# Power.net
KiCad netlist of a schematic drawn in Altium Designer
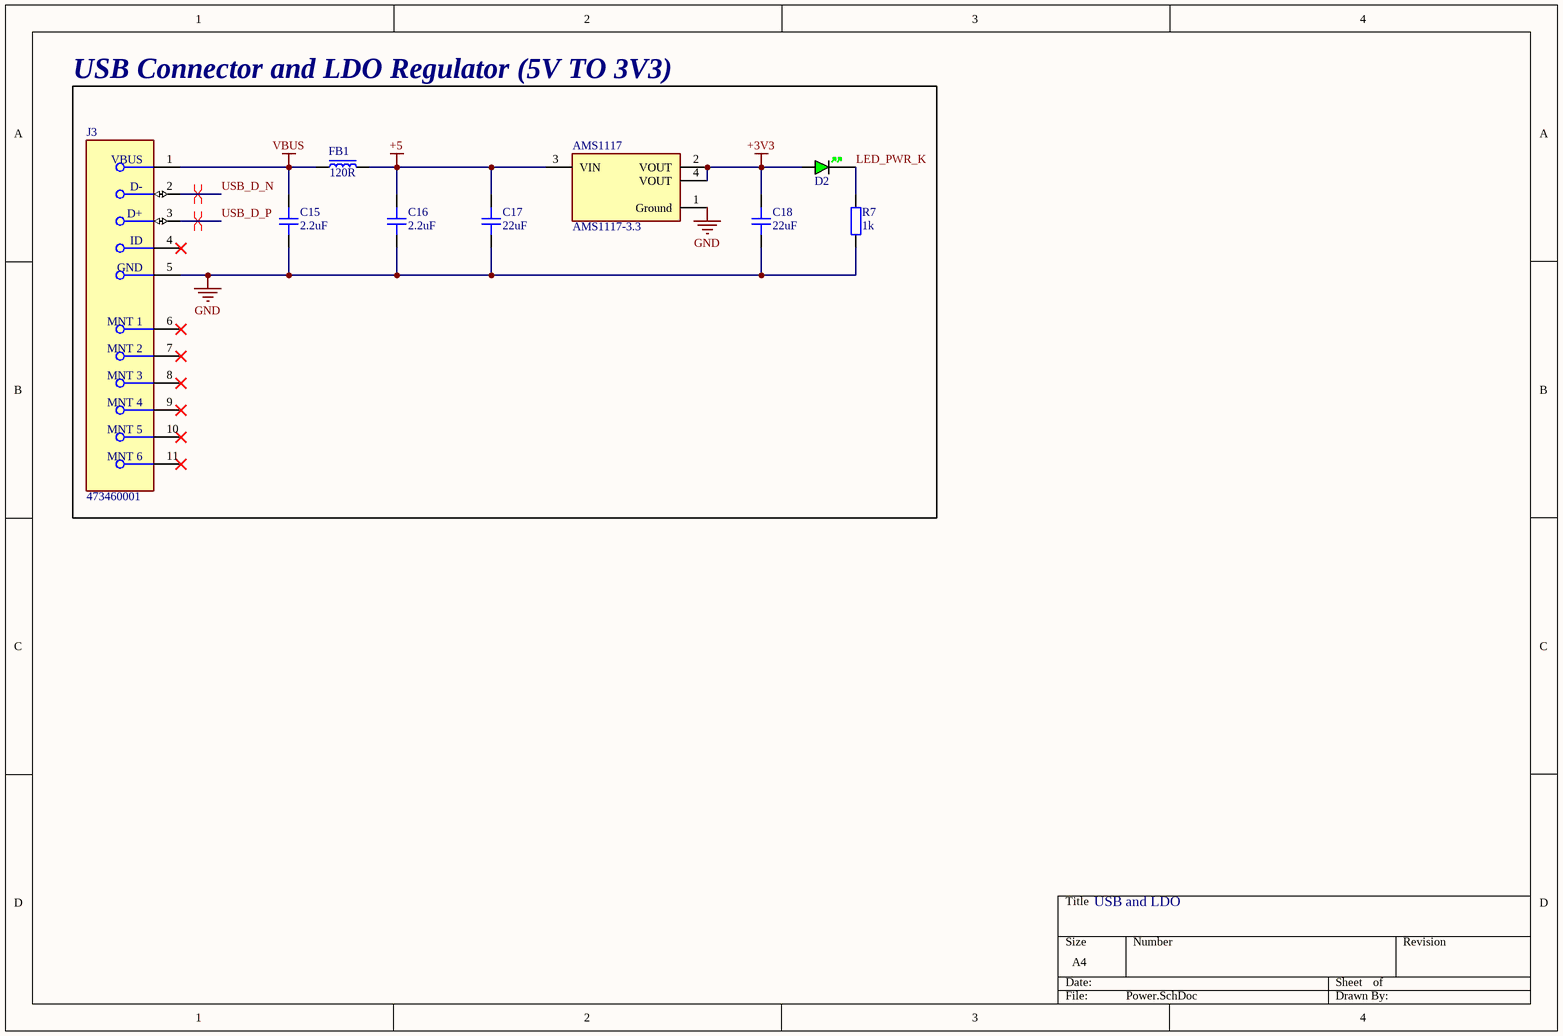
[diagram p0: Power.SchDoc]

(export (version "E")
  (design (tool "Eeschema 10.0.6"))
  (components
    (comp (ref "AMS1117")
      (value "AMS1117-3.3")
      (footprint "FP-AMS1117-IPC_C")
      (description "LDO Voltage Regulators 1A, 3.3V")
      (fields
        (field (name "OCTOPART") "https://octopart.com/ams1117-3.3-advanced+monolithic+systems-25899300")
        (field (name "MANUFACTURER") "Advanced Monolithic Systems")
      )
      (libsource (lib "Altium Content Vault") (part "8bdbb5f8e77002000e30dd2845d0354"))
    )
    (comp (ref "C15")
      (value "2.2uF")
      (footprint "CAP_0603")
      (description "Capacitor SMD 0603")
      (libsource (lib "Schematic-Lib-PhilsLab") (part "CAP_0603"))
    )
    (comp (ref "C16")
      (value "2.2uF")
      (footprint "CAP_0603")
      (description "Capacitor SMD 0603")
      (libsource (lib "Schematic-Lib-PhilsLab") (part "CAP_0603"))
    )
    (comp (ref "C17")
      (value "22uF")
      (footprint "CAP_0805")
      (description "Capacitor SMD 0805")
      (libsource (lib "Schematic-Lib-PhilsLab") (part "CAP_0805"))
    )
    (comp (ref "C18")
      (value "22uF")
      (footprint "CAP_0805")
      (description "Capacitor SMD 0805")
      (libsource (lib "Schematic-Lib-PhilsLab") (part "CAP_0805"))
    )
    (comp (ref "D2")
      (value "GREEN")
      (footprint "LED_0402_GREEN")
      (description "LED 0402 GREEN SMD")
      (libsource (lib "Schematic-Lib-PhilsLab") (part "LED_0402_GREEN"))
    )
    (comp (ref "FB1")
      (value "120R")
      (footprint "FB_0603")
      (description "Ferrite Bead SMD 0603")
      (libsource (lib "Schematic-Lib-PhilsLab") (part "FB_0603"))
    )
    (comp (ref "J3")
      (value "473460001")
      (footprint "FP-473460001-MFG")
      (description "CONN RCPT USB2.0 MICRO B SMD R/A")
      (fields
        (field (name "OCTOPART") "https://octopart.com/47346-0001-molex-7164928")
        (field (name "MANUFACTURER") "Molex")
      )
      (libsource (lib "Altium Content Vault") (part "53ae1f1d9b557310b43ca686e5bb76a"))
    )
    (comp (ref "R7")
      (value "1k")
      (footprint "RES_0402")
      (description "Resistor SMD 0402")
      (libsource (lib "Schematic-Lib-PhilsLab") (part "RES_0402"))
    )
  )
  (nets
    (net (code "1") (name "+3V3") (class "Default")
      (node (ref "AMS1117") (pin "2") (pinfunction "VOUT_2") (pintype "passive"))
      (node (ref "AMS1117") (pin "4") (pinfunction "VOUT_4") (pintype "passive"))
      (node (ref "C18") (pin "2") (pinfunction "2_2") (pintype "passive"))
      (node (ref "D2") (pin "A") (pinfunction "A_A") (pintype "passive"))
    )
    (net (code "2") (name "+5") (class "Default")
      (node (ref "AMS1117") (pin "3") (pinfunction "VIN_3") (pintype "power_in"))
      (node (ref "C16") (pin "2") (pinfunction "2_2") (pintype "passive"))
      (node (ref "C17") (pin "2") (pinfunction "2_2") (pintype "passive"))
      (node (ref "FB1") (pin "2") (pinfunction "2_2") (pintype "passive"))
    )
    (net (code "3") (name "/LED_PWR_K") (class "Default")
      (node (ref "D2") (pin "K") (pinfunction "K_K") (pintype "passive"))
      (node (ref "R7") (pin "2") (pinfunction "2_2") (pintype "passive"))
    )
    (net (code "4") (name "/USB_D_N") (class "Default")
      (node (ref "J3") (pin "2") (pinfunction "D-_2") (pintype "bidirectional"))
    )
    (net (code "5") (name "/USB_D_P") (class "Default")
      (node (ref "J3") (pin "3") (pinfunction "D+_3") (pintype "bidirectional"))
    )
    (net (code "6") (name "GND") (class "Default")
      (node (ref "AMS1117") (pin "1") (pinfunction "Ground_1") (pintype "power_in"))
      (node (ref "C15") (pin "1") (pinfunction "1_1") (pintype "passive"))
      (node (ref "C16") (pin "1") (pinfunction "1_1") (pintype "passive"))
      (node (ref "C17") (pin "1") (pinfunction "1_1") (pintype "passive"))
      (node (ref "C18") (pin "1") (pinfunction "1_1") (pintype "passive"))
      (node (ref "J3") (pin "5") (pinfunction "GND_5") (pintype "power_in"))
      (node (ref "R7") (pin "1") (pinfunction "1_1") (pintype "passive"))
    )
    (net (code "7") (name "VBUS") (class "Default")
      (node (ref "C15") (pin "2") (pinfunction "2_2") (pintype "passive"))
      (node (ref "FB1") (pin "1") (pinfunction "1_1") (pintype "passive"))
      (node (ref "J3") (pin "1") (pinfunction "VBUS_1") (pintype "power_in"))
    )
    (net (code "8") (name "unconnected-(J3-ID-Pad4)") (class "Default")
      (node (ref "J3") (pin "4") (pinfunction "ID_4") (pintype "passive+no_connect"))
    )
    (net (code "9") (name "unconnected-(J3-MNT_1-Pad6)") (class "Default")
      (node (ref "J3") (pin "6") (pinfunction "MNT_1_6") (pintype "passive+no_connect"))
    )
    (net (code "10") (name "unconnected-(J3-MNT_2-Pad7)") (class "Default")
      (node (ref "J3") (pin "7") (pinfunction "MNT_2_7") (pintype "passive+no_connect"))
    )
    (net (code "11") (name "unconnected-(J3-MNT_3-Pad8)") (class "Default")
      (node (ref "J3") (pin "8") (pinfunction "MNT_3_8") (pintype "passive+no_connect"))
    )
    (net (code "12") (name "unconnected-(J3-MNT_4-Pad9)") (class "Default")
      (node (ref "J3") (pin "9") (pinfunction "MNT_4_9") (pintype "passive+no_connect"))
    )
    (net (code "13") (name "unconnected-(J3-MNT_5-Pad10)") (class "Default")
      (node (ref "J3") (pin "10") (pinfunction "MNT_5_10") (pintype "passive+no_connect"))
    )
    (net (code "14") (name "unconnected-(J3-MNT_6-Pad11)") (class "Default")
      (node (ref "J3") (pin "11") (pinfunction "MNT_6_11") (pintype "passive+no_connect"))
    )
  )
)
